# Sender.net
KiCad netlist of a schematic drawn in Altium Designer
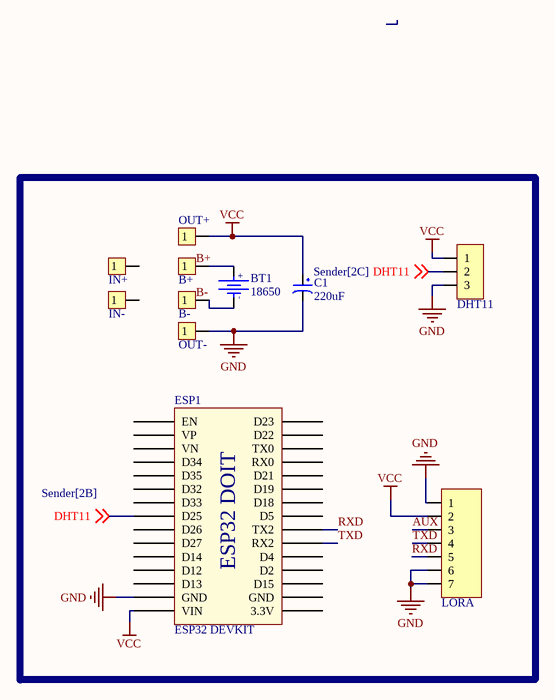
[diagram p0: Sender.SchDoc]

(export (version "E")
  (design (tool "Eeschema 10.0.6"))
  (components
    (comp (ref "BT1")
      (value "18650")
      (footprint "De Pin18650")
      (libsource (lib "Lib_SCH_VanThiet") (part "De Pin18650"))
    )
    (comp (ref "C1")
      (value "220uF")
      (footprint "Tu hoa 8mm")
      (description "Cắm")
      (libsource (lib "Altium_Lib_by_KhueNguyenCreator") (part "Tu Hoa 220uF 25V 8x10"))
    )
    (comp (ref "ESP1")
      (value "ESP32 DEVKIT")
      (footprint "ESP32 WROOM 32 KIT")
      (libsource (lib "Altium_Lib_by_KhueNguyenCreator") (part "ESP32 WROOM 32 KIT"))
    )
    (comp (ref "JP1")
      (value "OUT+")
      (footprint "JP 1x1 DT")
      (description "Cắm")
      (libsource (lib "Altium_Lib_by_KhueNguyenCreator") (part "JP 1x1 2.54 Duc Thang"))
    )
    (comp (ref "JP2")
      (value "LORA")
      (footprint "JP 1x7 CT")
      (description "Cắm")
      (libsource (lib "Altium_Lib_by_KhueNguyenCreator") (part "JP 1x7 2.54 Cai Thang"))
    )
    (comp (ref "JP3")
      (value "IN+")
      (footprint "JP 1x1 DT")
      (description "Cắm")
      (libsource (lib "Altium_Lib_by_KhueNguyenCreator") (part "JP 1x1 2.54 Duc Thang"))
    )
    (comp (ref "JP4")
      (value "B+")
      (footprint "JP 1x1 DT")
      (description "Cắm")
      (libsource (lib "Altium_Lib_by_KhueNguyenCreator") (part "JP 1x1 2.54 Duc Thang"))
    )
    (comp (ref "JP5")
      (value "IN-")
      (footprint "JP 1x1 DT")
      (description "Cắm")
      (libsource (lib "Altium_Lib_by_KhueNguyenCreator") (part "JP 1x1 2.54 Duc Thang"))
    )
    (comp (ref "JP6")
      (value "B-")
      (footprint "JP 1x1 DT")
      (description "Cắm")
      (libsource (lib "Altium_Lib_by_KhueNguyenCreator") (part "JP 1x1 2.54 Duc Thang"))
    )
    (comp (ref "JP7")
      (value "OUT-")
      (footprint "JP 1x1 DT")
      (description "Cắm")
      (libsource (lib "Altium_Lib_by_KhueNguyenCreator") (part "JP 1x1 2.54 Duc Thang"))
    )
    (comp (ref "JP8")
      (value "DHT11")
      (footprint "JP 1x3 CT")
      (description "Cắm")
      (libsource (lib "Altium_Lib_by_KhueNguyenCreator") (part "JP 1x3 2.54 Cai Thang"))
    )
  )
  (nets
    (net (code "1") (name "/AUX") (class "Default")
      (node (ref "JP2") (pin "3") (pinfunction "3_3") (pintype "passive"))
    )
    (net (code "4") (name "/RXD") (class "Default")
      (node (ref "ESP1") (pin "22") (pinfunction "TX2_22") (pintype "passive"))
      (node (ref "JP2") (pin "5") (pinfunction "5_5") (pintype "passive"))
    )
    (net (code "5") (name "/TXD") (class "Default")
      (node (ref "ESP1") (pin "21") (pinfunction "RX2_21") (pintype "passive"))
      (node (ref "JP2") (pin "4") (pinfunction "4_4") (pintype "passive"))
    )
    (net (code "6") (name "DHT11") (class "Default")
      (node (ref "ESP1") (pin "8") (pinfunction "D25_8") (pintype "passive"))
      (node (ref "JP8") (pin "2") (pinfunction "2_2") (pintype "passive"))
    )
    (net (code "7") (name "GND") (class "Default")
      (node (ref "C1") (pin "2") (pinfunction "2_2") (pintype "passive"))
      (node (ref "ESP1") (pin "14") (pinfunction "GND_14") (pintype "passive"))
      (node (ref "JP2") (pin "1") (pinfunction "1_1") (pintype "passive"))
      (node (ref "JP2") (pin "6") (pinfunction "6_6") (pintype "passive"))
      (node (ref "JP2") (pin "7") (pinfunction "7_7") (pintype "passive"))
      (node (ref "JP7") (pin "1") (pinfunction "1_1") (pintype "passive"))
      (node (ref "JP8") (pin "3") (pinfunction "3_3") (pintype "passive"))
    )
    (net (code "8") (name "Net-(BT1-GND)") (class "Default")
      (node (ref "BT1") (pin "2") (pinfunction "GND_2") (pintype "passive"))
      (node (ref "JP6") (pin "1") (pinfunction "1_1") (pintype "passive"))
    )
    (net (code "9") (name "Net-(BT1-VCC)") (class "Default")
      (node (ref "BT1") (pin "1") (pinfunction "VCC_1") (pintype "passive"))
      (node (ref "JP4") (pin "1") (pinfunction "1_1") (pintype "passive"))
    )
    (net (code "10") (name "VCC") (class "Default")
      (node (ref "C1") (pin "1") (pinfunction "1_1") (pintype "passive"))
      (node (ref "ESP1") (pin "15") (pinfunction "VIN_15") (pintype "passive"))
      (node (ref "JP1") (pin "1") (pinfunction "1_1") (pintype "passive"))
      (node (ref "JP2") (pin "2") (pinfunction "2_2") (pintype "passive"))
      (node (ref "JP8") (pin "1") (pinfunction "1_1") (pintype "passive"))
    )
    (net (code "11") (name "unconnected-(ESP1-3.3V-Pad16)") (class "Default")
      (node (ref "ESP1") (pin "16") (pinfunction "3.3V_16") (pintype "passive"))
    )
    (net (code "12") (name "unconnected-(ESP1-D2-Pad19)") (class "Default")
      (node (ref "ESP1") (pin "19") (pinfunction "D2_19") (pintype "passive"))
    )
    (net (code "13") (name "unconnected-(ESP1-D4-Pad20)") (class "Default")
      (node (ref "ESP1") (pin "20") (pinfunction "D4_20") (pintype "passive"))
    )
    (net (code "14") (name "unconnected-(ESP1-D5-Pad23)") (class "Default")
      (node (ref "ESP1") (pin "23") (pinfunction "D5_23") (pintype "passive"))
    )
    (net (code "15") (name "unconnected-(ESP1-D12-Pad12)") (class "Default")
      (node (ref "ESP1") (pin "12") (pinfunction "D12_12") (pintype "passive"))
    )
    (net (code "16") (name "unconnected-(ESP1-D13-Pad13)") (class "Default")
      (node (ref "ESP1") (pin "13") (pinfunction "D13_13") (pintype "passive"))
    )
    (net (code "17") (name "unconnected-(ESP1-D14-Pad11)") (class "Default")
      (node (ref "ESP1") (pin "11") (pinfunction "D14_11") (pintype "passive"))
    )
    (net (code "18") (name "unconnected-(ESP1-D15-Pad18)") (class "Default")
      (node (ref "ESP1") (pin "18") (pinfunction "D15_18") (pintype "passive"))
    )
    (net (code "19") (name "unconnected-(ESP1-D18-Pad24)") (class "Default")
      (node (ref "ESP1") (pin "24") (pinfunction "D18_24") (pintype "passive"))
    )
    (net (code "20") (name "unconnected-(ESP1-D19-Pad25)") (class "Default")
      (node (ref "ESP1") (pin "25") (pinfunction "D19_25") (pintype "passive"))
    )
    (net (code "21") (name "unconnected-(ESP1-D21-Pad26)") (class "Default")
      (node (ref "ESP1") (pin "26") (pinfunction "D21_26") (pintype "passive"))
    )
    (net (code "22") (name "unconnected-(ESP1-D22-Pad29)") (class "Default")
      (node (ref "ESP1") (pin "29") (pinfunction "D22_29") (pintype "passive"))
    )
    (net (code "23") (name "unconnected-(ESP1-D23-Pad30)") (class "Default")
      (node (ref "ESP1") (pin "30") (pinfunction "D23_30") (pintype "passive"))
    )
    (net (code "24") (name "unconnected-(ESP1-D26-Pad9)") (class "Default")
      (node (ref "ESP1") (pin "9") (pinfunction "D26_9") (pintype "passive"))
    )
    (net (code "25") (name "unconnected-(ESP1-D27-Pad10)") (class "Default")
      (node (ref "ESP1") (pin "10") (pinfunction "D27_10") (pintype "passive"))
    )
    (net (code "26") (name "unconnected-(ESP1-D32-Pad6)") (class "Default")
      (node (ref "ESP1") (pin "6") (pinfunction "D32_6") (pintype "passive"))
    )
    (net (code "27") (name "unconnected-(ESP1-D33-Pad7)") (class "Default")
      (node (ref "ESP1") (pin "7") (pinfunction "D33_7") (pintype "passive"))
    )
    (net (code "28") (name "unconnected-(ESP1-D34-Pad4)") (class "Default")
      (node (ref "ESP1") (pin "4") (pinfunction "D34_4") (pintype "passive"))
    )
    (net (code "29") (name "unconnected-(ESP1-D35-Pad5)") (class "Default")
      (node (ref "ESP1") (pin "5") (pinfunction "D35_5") (pintype "passive"))
    )
    (net (code "30") (name "unconnected-(ESP1-EN-Pad1)") (class "Default")
      (node (ref "ESP1") (pin "1") (pinfunction "EN_1") (pintype "passive"))
    )
    (net (code "31") (name "unconnected-(ESP1-GND-Pad17)") (class "Default")
      (node (ref "ESP1") (pin "17") (pinfunction "GND_17") (pintype "passive"))
    )
    (net (code "32") (name "unconnected-(ESP1-RX0-Pad27)") (class "Default")
      (node (ref "ESP1") (pin "27") (pinfunction "RX0_27") (pintype "passive"))
    )
    (net (code "33") (name "unconnected-(ESP1-TX0-Pad28)") (class "Default")
      (node (ref "ESP1") (pin "28") (pinfunction "TX0_28") (pintype "passive"))
    )
    (net (code "34") (name "unconnected-(ESP1-VN-Pad3)") (class "Default")
      (node (ref "ESP1") (pin "3") (pinfunction "VN_3") (pintype "passive"))
    )
    (net (code "35") (name "unconnected-(ESP1-VP-Pad2)") (class "Default")
      (node (ref "ESP1") (pin "2") (pinfunction "VP_2") (pintype "passive"))
    )
    (net (code "36") (name "unconnected-(JP3-Pad1)") (class "Default")
      (node (ref "JP3") (pin "1") (pinfunction "1_1") (pintype "passive"))
    )
    (net (code "37") (name "unconnected-(JP5-Pad1)") (class "Default")
      (node (ref "JP5") (pin "1") (pinfunction "1_1") (pintype "passive"))
    )
  )
)
